# Sheet1.net
KiCad netlist of a schematic drawn in Altium Designer
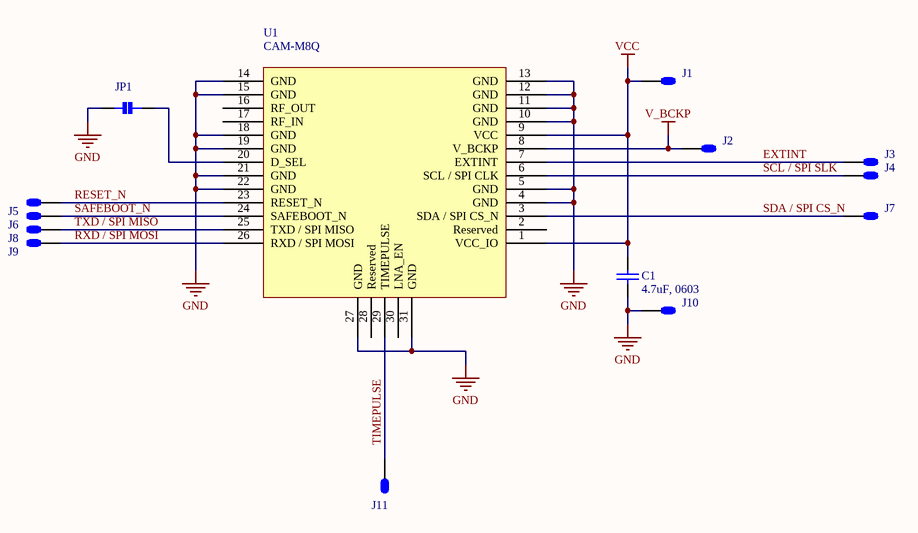
[diagram p0: Sheet1.SchDoc]

(export (version "E")
  (design (tool "Eeschema 10.0.6"))
  (components
    (comp (ref "C1")
      (value "4.7uF, 0603")
      (footprint "Capacitor 0603")
      (libsource (lib "x-io") (part "Capacitor"))
    )
    (comp (ref "J1")
      (value "Wire To Board Solder Pad")
      (footprint "Wire To Board Solder Pad")
      (libsource (lib "x-io") (part "Wire To Board Solder Pad"))
    )
    (comp (ref "J2")
      (value "Wire To Board Solder Pad")
      (footprint "Wire To Board Solder Pad")
      (libsource (lib "x-io") (part "Wire To Board Solder Pad"))
    )
    (comp (ref "J3")
      (value "Wire To Board Solder Pad")
      (footprint "Wire To Board Solder Pad")
      (libsource (lib "x-io") (part "Wire To Board Solder Pad"))
    )
    (comp (ref "J4")
      (value "Wire To Board Solder Pad")
      (footprint "Wire To Board Solder Pad")
      (libsource (lib "x-io") (part "Wire To Board Solder Pad"))
    )
    (comp (ref "J5")
      (value "Wire To Board Solder Pad")
      (footprint "Wire To Board Solder Pad")
      (libsource (lib "x-io") (part "Wire To Board Solder Pad"))
    )
    (comp (ref "J6")
      (value "Wire To Board Solder Pad")
      (footprint "Wire To Board Solder Pad")
      (libsource (lib "x-io") (part "Wire To Board Solder Pad"))
    )
    (comp (ref "J7")
      (value "Wire To Board Solder Pad")
      (footprint "Wire To Board Solder Pad")
      (libsource (lib "x-io") (part "Wire To Board Solder Pad"))
    )
    (comp (ref "J8")
      (value "Wire To Board Solder Pad")
      (footprint "Wire To Board Solder Pad")
      (libsource (lib "x-io") (part "Wire To Board Solder Pad"))
    )
    (comp (ref "J9")
      (value "Wire To Board Solder Pad")
      (footprint "Wire To Board Solder Pad")
      (libsource (lib "x-io") (part "Wire To Board Solder Pad"))
    )
    (comp (ref "J10")
      (value "Wire To Board Solder Pad")
      (footprint "Wire To Board Solder Pad")
      (libsource (lib "x-io") (part "Wire To Board Solder Pad"))
    )
    (comp (ref "J11")
      (value "Wire To Board Solder Pad")
      (footprint "Wire To Board Solder Pad")
      (libsource (lib "x-io") (part "Wire To Board Solder Pad"))
    )
    (comp (ref "JP1")
      (value "Solder Jumper")
      (footprint "Solder Jumper")
      (libsource (lib "x-io") (part "Solder Jumper"))
    )
    (comp (ref "U1") (value "CAM-M8Q") (footprint "CAM-M8Q") (libsource (lib "x-io") (part "CAM-M8Q")))
  )
  (nets
    (net (code "1") (name "/EXTINT") (class "Default")
      (node (ref "J3") (pin "1") (pinfunction "1_1") (pintype "passive"))
      (node (ref "U1") (pin "7") (pinfunction "EXTINT_7") (pintype "passive"))
    )
    (net (code "2") (name "/RESET_N") (class "Default")
      (node (ref "J5") (pin "1") (pinfunction "1_1") (pintype "passive"))
      (node (ref "U1") (pin "23") (pinfunction "RESET_N_23") (pintype "passive"))
    )
    (net (code "3") (name "/RXD {slash} SPI MOSI") (class "Default")
      (node (ref "J9") (pin "1") (pinfunction "1_1") (pintype "passive"))
      (node (ref "U1") (pin "26") (pinfunction "RXD_/_SPI_MOSI_26") (pintype "passive"))
    )
    (net (code "4") (name "/SAFEBOOT_N") (class "Default")
      (node (ref "J6") (pin "1") (pinfunction "1_1") (pintype "passive"))
      (node (ref "U1") (pin "24") (pinfunction "SAFEBOOT_N_24") (pintype "passive"))
    )
    (net (code "5") (name "/SCL {slash} SPI SLK") (class "Default")
      (node (ref "J4") (pin "1") (pinfunction "1_1") (pintype "passive"))
      (node (ref "U1") (pin "6") (pinfunction "SCL_/_SPI_CLK_6") (pintype "passive"))
    )
    (net (code "6") (name "/SDA {slash} SPI CS_N") (class "Default")
      (node (ref "J7") (pin "1") (pinfunction "1_1") (pintype "passive"))
      (node (ref "U1") (pin "3") (pinfunction "SDA_/_SPI_CS_N_3") (pintype "passive"))
    )
    (net (code "7") (name "/TIMEPULSE") (class "Default")
      (node (ref "J11") (pin "1") (pinfunction "1_1") (pintype "passive"))
      (node (ref "U1") (pin "29") (pinfunction "TIMEPULSE_29") (pintype "passive"))
    )
    (net (code "8") (name "/TXD {slash} SPI MISO") (class "Default")
      (node (ref "J8") (pin "1") (pinfunction "1_1") (pintype "passive"))
      (node (ref "U1") (pin "25") (pinfunction "TXD_/_SPI_MISO_25") (pintype "passive"))
    )
    (net (code "9") (name "GND") (class "Default")
      (node (ref "C1") (pin "1") (pinfunction "1_1") (pintype "passive"))
      (node (ref "J10") (pin "1") (pinfunction "1_1") (pintype "passive"))
      (node (ref "JP1") (pin "1") (pinfunction "1_1") (pintype "passive"))
      (node (ref "U1") (pin "10") (pinfunction "GND_10") (pintype "passive"))
      (node (ref "U1") (pin "11") (pinfunction "GND_11") (pintype "passive"))
      (node (ref "U1") (pin "12") (pinfunction "GND_12") (pintype "passive"))
      (node (ref "U1") (pin "13") (pinfunction "GND_13") (pintype "passive"))
      (node (ref "U1") (pin "14") (pinfunction "GND_14") (pintype "passive"))
      (node (ref "U1") (pin "15") (pinfunction "GND_15") (pintype "passive"))
      (node (ref "U1") (pin "18") (pinfunction "GND_18") (pintype "passive"))
      (node (ref "U1") (pin "19") (pinfunction "GND_19") (pintype "passive"))
      (node (ref "U1") (pin "21") (pinfunction "GND_21") (pintype "passive"))
      (node (ref "U1") (pin "22") (pinfunction "GND_22") (pintype "passive"))
      (node (ref "U1") (pin "27") (pinfunction "GND_27") (pintype "passive"))
      (node (ref "U1") (pin "31") (pinfunction "GND_31") (pintype "passive"))
      (node (ref "U1") (pin "4") (pinfunction "GND_4") (pintype "passive"))
      (node (ref "U1") (pin "5") (pinfunction "GND_5") (pintype "passive"))
    )
    (net (code "10") (name "Net-(U1-D_SEL)") (class "Default")
      (node (ref "JP1") (pin "2") (pinfunction "2_2") (pintype "passive"))
      (node (ref "U1") (pin "20") (pinfunction "D_SEL_20") (pintype "passive"))
    )
    (net (code "11") (name "VCC") (class "Default")
      (node (ref "C1") (pin "2") (pinfunction "2_2") (pintype "passive"))
      (node (ref "J1") (pin "1") (pinfunction "1_1") (pintype "passive"))
      (node (ref "U1") (pin "1") (pinfunction "VCC_IO_1") (pintype "passive"))
      (node (ref "U1") (pin "9") (pinfunction "VCC_9") (pintype "passive"))
    )
    (net (code "12") (name "V_BCKP") (class "Default")
      (node (ref "J2") (pin "1") (pinfunction "1_1") (pintype "passive"))
      (node (ref "U1") (pin "8") (pinfunction "V_BCKP_8") (pintype "passive"))
    )
    (net (code "13") (name "unconnected-(U1-LNA_EN-Pad30)") (class "Default")
      (node (ref "U1") (pin "30") (pinfunction "LNA_EN_30") (pintype "passive"))
    )
    (net (code "14") (name "unconnected-(U1-RF_IN-Pad17)") (class "Default")
      (node (ref "U1") (pin "17") (pinfunction "RF_IN_17") (pintype "passive"))
    )
    (net (code "15") (name "unconnected-(U1-RF_OUT-Pad16)") (class "Default")
      (node (ref "U1") (pin "16") (pinfunction "RF_OUT_16") (pintype "passive"))
    )
    (net (code "16") (name "unconnected-(U1-Reserved-Pad2)") (class "Default")
      (node (ref "U1") (pin "2") (pinfunction "Reserved_2") (pintype "passive"))
    )
    (net (code "17") (name "unconnected-(U1-Reserved-Pad28)") (class "Default")
      (node (ref "U1") (pin "28") (pinfunction "Reserved_28") (pintype "passive"))
    )
  )
)
